# LCD.net
KiCad netlist of a schematic drawn in Altium Designer
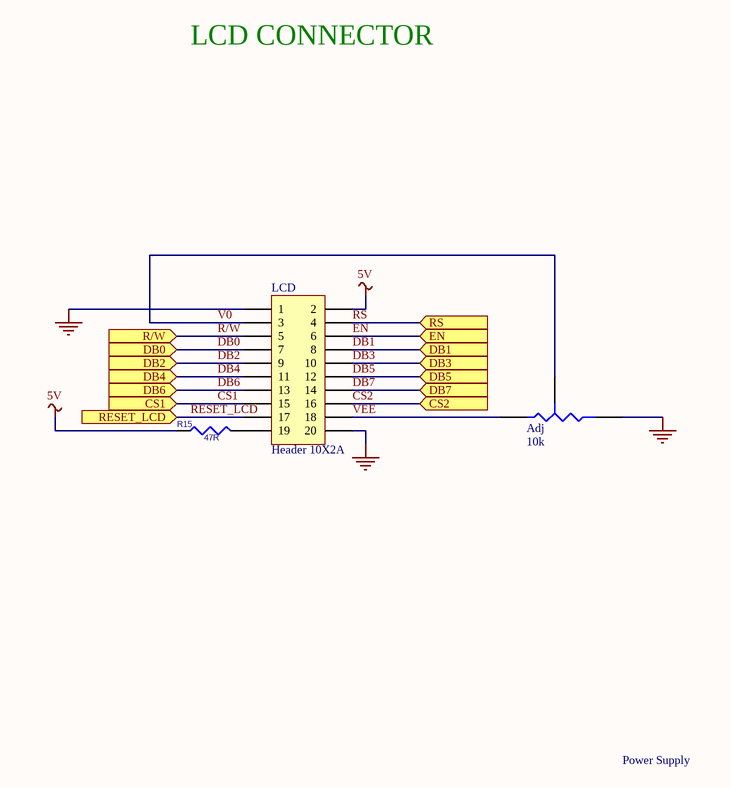
[diagram p0: LCD.SchDoc]

(export (version "E")
  (design (tool "Eeschema 10.0.6"))
  (components
    (comp (ref "Adj")
      (value "10k")
      (footprint "Pot 3pin")
      (description "Tapped Resistor")
      (fields (field (name "Comment") "RES_POT") (field (name "PUBLISHER") "Altium Limited"))
      (libsource (lib "combined_cart_schematic_lib") (part "RES_POT"))
    )
    (comp (ref "LCD")
      (value "Header 10X2A")
      (footprint "10x2 row_ 2.54mm pitch")
      (description "Header, 20Pin, Dual row")
      (fields (field (name "PUBLISHER") "Altium Limited"))
      (libsource (lib "combined_cart_schematic_lib") (part "Header 10x2"))
    )
    (comp (ref "R15")
      (value "47R")
      (footprint "RES_SMD")
      (libsource (lib "combined_cart_schematic_lib") (part "RESISTOR"))
    )
  )
  (nets
    (net (code "1") (name "/CS1") (class "Default")
      (node (ref "LCD") (pin "15") (pinfunction "15_15") (pintype "passive"))
    )
    (net (code "2") (name "/CS2") (class "Default")
      (node (ref "LCD") (pin "16") (pinfunction "16_16") (pintype "passive"))
    )
    (net (code "3") (name "/DB0") (class "Default")
      (node (ref "LCD") (pin "7") (pinfunction "7_7") (pintype "passive"))
    )
    (net (code "4") (name "/DB1") (class "Default")
      (node (ref "LCD") (pin "8") (pinfunction "8_8") (pintype "passive"))
    )
    (net (code "5") (name "/DB2") (class "Default")
      (node (ref "LCD") (pin "9") (pinfunction "9_9") (pintype "passive"))
    )
    (net (code "6") (name "/DB3") (class "Default")
      (node (ref "LCD") (pin "10") (pinfunction "10_10") (pintype "passive"))
    )
    (net (code "7") (name "/DB4") (class "Default")
      (node (ref "LCD") (pin "11") (pinfunction "11_11") (pintype "passive"))
    )
    (net (code "8") (name "/DB5") (class "Default")
      (node (ref "LCD") (pin "12") (pinfunction "12_12") (pintype "passive"))
    )
    (net (code "9") (name "/DB6") (class "Default")
      (node (ref "LCD") (pin "13") (pinfunction "13_13") (pintype "passive"))
    )
    (net (code "10") (name "/DB7") (class "Default")
      (node (ref "LCD") (pin "14") (pinfunction "14_14") (pintype "passive"))
    )
    (net (code "11") (name "/EN") (class "Default")
      (node (ref "LCD") (pin "6") (pinfunction "6_6") (pintype "passive"))
    )
    (net (code "12") (name "/RESET_LCD") (class "Default")
      (node (ref "LCD") (pin "17") (pinfunction "17_17") (pintype "passive"))
    )
    (net (code "13") (name "/RS") (class "Default")
      (node (ref "LCD") (pin "4") (pinfunction "4_4") (pintype "passive"))
    )
    (net (code "14") (name "/R{slash}W") (class "Default")
      (node (ref "LCD") (pin "5") (pinfunction "5_5") (pintype "passive"))
    )
    (net (code "15") (name "/V0") (class "Default")
      (node (ref "Adj") (pin "2") (pinfunction "TAP_2") (pintype "passive"))
      (node (ref "LCD") (pin "3") (pinfunction "3_3") (pintype "passive"))
    )
    (net (code "16") (name "/VEE") (class "Default")
      (node (ref "Adj") (pin "1") (pinfunction "A_1") (pintype "passive"))
      (node (ref "LCD") (pin "18") (pinfunction "18_18") (pintype "passive"))
    )
    (net (code "17") (name "5V") (class "Default")
      (node (ref "LCD") (pin "2") (pinfunction "2_2") (pintype "passive"))
      (node (ref "R15") (pin "1") (pinfunction "1_1") (pintype "passive"))
    )
    (net (code "18") (name "GND_POWER") (class "Default")
      (node (ref "Adj") (pin "3") (pinfunction "B_3") (pintype "passive"))
      (node (ref "LCD") (pin "1") (pinfunction "1_1") (pintype "passive"))
      (node (ref "LCD") (pin "20") (pinfunction "20_20") (pintype "passive"))
    )
    (net (code "19") (name "Net-(LCD-Pad19)") (class "Default")
      (node (ref "LCD") (pin "19") (pinfunction "19_19") (pintype "passive"))
      (node (ref "R15") (pin "2") (pinfunction "2_2") (pintype "passive"))
    )
  )
)
